# remote_v3.net
KiCad netlist of a schematic drawn in EAGLE
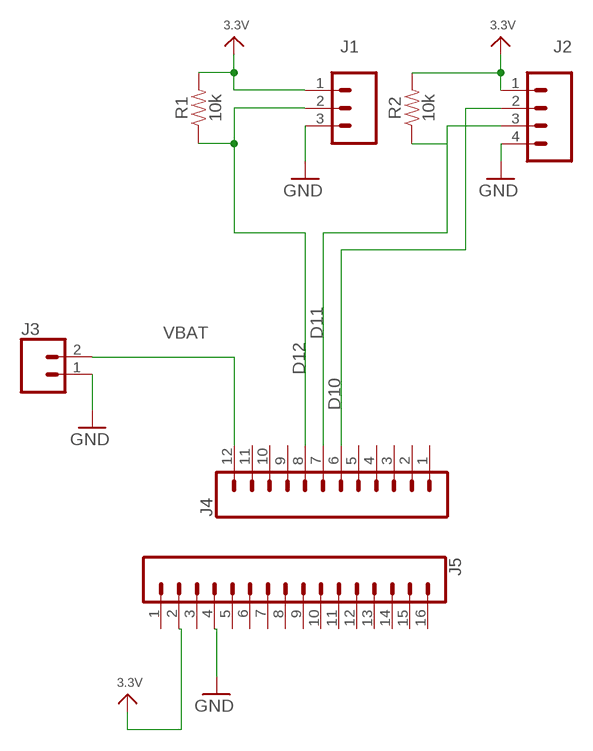
[diagram p0: schematic, sheet 1]

(export (version "E")
  (design (tool "Eeschema 10.0.6"))
  (components
    (comp (ref "J1")
      (value "CONN_03SCREW")
      (footprint "eagle-import:SCREWTERMINAL-3.5MM-3")
      (libsource (lib "eagle-import") (part "CONN_03SCREW"))
    )
    (comp (ref "J2")
      (value "CONN_04SCREW")
      (footprint "eagle-import:SCREWTERMINAL-3.5MM-4")
      (libsource (lib "eagle-import") (part "CONN_04SCREW"))
    )
    (comp (ref "J3")
      (value "CONN_023.5MM")
      (footprint "eagle-import:SCREWTERMINAL-3.5MM-2")
      (libsource (lib "eagle-import") (part "CONN_023.5MM"))
    )
    (comp (ref "J4")
      (value "CONN_12")
      (footprint "eagle-import:1X12")
      (libsource (lib "eagle-import") (part "CONN_12"))
    )
    (comp (ref "J5")
      (value "CONN_16")
      (footprint "eagle-import:1X16")
      (libsource (lib "eagle-import") (part "CONN_16"))
    )
    (comp (ref "R1")
      (value "10k")
      (footprint "eagle-import:AXIAL-0.3")
      (libsource (lib "eagle-import") (part "10KOHM-HORIZ-1/4W-1%"))
    )
    (comp (ref "R2")
      (value "10k")
      (footprint "eagle-import:AXIAL-0.3")
      (libsource (lib "eagle-import") (part "10KOHM-HORIZ-1/4W-1%"))
    )
  )
  (nets
    (net (code "1") (name "/D10") (class "Default")
      (node (ref "J2") (pin "2") (pinfunction "2_2") (pintype "passive"))
      (node (ref "J4") (pin "6") (pinfunction "6_6") (pintype "passive"))
    )
    (net (code "2") (name "/D11") (class "Default")
      (node (ref "J2") (pin "3") (pinfunction "3_3") (pintype "passive"))
      (node (ref "J4") (pin "7") (pinfunction "7_7") (pintype "passive"))
      (node (ref "R2") (pin "P$1") (pinfunction "1_P$1") (pintype "passive"))
    )
    (net (code "3") (name "/D12") (class "Default")
      (node (ref "J1") (pin "2") (pinfunction "2_2") (pintype "passive"))
      (node (ref "J4") (pin "8") (pinfunction "8_8") (pintype "passive"))
      (node (ref "R1") (pin "P$1") (pinfunction "1_P$1") (pintype "passive"))
    )
    (net (code "4") (name "/VBAT") (class "Default")
      (node (ref "J3") (pin "2") (pinfunction "2_2") (pintype "passive"))
      (node (ref "J4") (pin "12") (pinfunction "12_12") (pintype "passive"))
    )
    (net (code "5") (name "3.3V") (class "Default")
      (node (ref "J1") (pin "1") (pinfunction "1_1") (pintype "passive"))
      (node (ref "J2") (pin "1") (pinfunction "1_1") (pintype "passive"))
      (node (ref "J5") (pin "2") (pinfunction "2_2") (pintype "passive"))
      (node (ref "R1") (pin "P$2") (pinfunction "2_P$2") (pintype "passive"))
      (node (ref "R2") (pin "P$2") (pinfunction "2_P$2") (pintype "passive"))
    )
    (net (code "6") (name "GND") (class "Default")
      (node (ref "J1") (pin "3") (pinfunction "3_3") (pintype "passive"))
      (node (ref "J2") (pin "4") (pinfunction "4_4") (pintype "passive"))
      (node (ref "J3") (pin "1") (pinfunction "1_1") (pintype "passive"))
      (node (ref "J5") (pin "4") (pinfunction "4_4") (pintype "passive"))
    )
    (net (code "7") (name "unconnected-(J4-Pad1)") (class "Default")
      (node (ref "J4") (pin "1") (pinfunction "1_1") (pintype "passive"))
    )
    (net (code "8") (name "unconnected-(J4-Pad2)") (class "Default")
      (node (ref "J4") (pin "2") (pinfunction "2_2") (pintype "passive"))
    )
    (net (code "9") (name "unconnected-(J4-Pad3)") (class "Default")
      (node (ref "J4") (pin "3") (pinfunction "3_3") (pintype "passive"))
    )
    (net (code "10") (name "unconnected-(J4-Pad4)") (class "Default")
      (node (ref "J4") (pin "4") (pinfunction "4_4") (pintype "passive"))
    )
    (net (code "11") (name "unconnected-(J4-Pad5)") (class "Default")
      (node (ref "J4") (pin "5") (pinfunction "5_5") (pintype "passive"))
    )
    (net (code "12") (name "unconnected-(J4-Pad9)") (class "Default")
      (node (ref "J4") (pin "9") (pinfunction "9_9") (pintype "passive"))
    )
    (net (code "13") (name "unconnected-(J4-Pad10)") (class "Default")
      (node (ref "J4") (pin "10") (pinfunction "10_10") (pintype "passive"))
    )
    (net (code "14") (name "unconnected-(J4-Pad11)") (class "Default")
      (node (ref "J4") (pin "11") (pinfunction "11_11") (pintype "passive"))
    )
    (net (code "15") (name "unconnected-(J5-Pad1)") (class "Default")
      (node (ref "J5") (pin "1") (pinfunction "1_1") (pintype "passive"))
    )
    (net (code "16") (name "unconnected-(J5-Pad3)") (class "Default")
      (node (ref "J5") (pin "3") (pinfunction "3_3") (pintype "passive"))
    )
    (net (code "17") (name "unconnected-(J5-Pad5)") (class "Default")
      (node (ref "J5") (pin "5") (pinfunction "5_5") (pintype "passive"))
    )
    (net (code "18") (name "unconnected-(J5-Pad6)") (class "Default")
      (node (ref "J5") (pin "6") (pinfunction "6_6") (pintype "passive"))
    )
    (net (code "19") (name "unconnected-(J5-Pad7)") (class "Default")
      (node (ref "J5") (pin "7") (pinfunction "7_7") (pintype "passive"))
    )
    (net (code "20") (name "unconnected-(J5-Pad8)") (class "Default")
      (node (ref "J5") (pin "8") (pinfunction "8_8") (pintype "passive"))
    )
    (net (code "21") (name "unconnected-(J5-Pad9)") (class "Default")
      (node (ref "J5") (pin "9") (pinfunction "9_9") (pintype "passive"))
    )
    (net (code "22") (name "unconnected-(J5-Pad10)") (class "Default")
      (node (ref "J5") (pin "10") (pinfunction "10_10") (pintype "passive"))
    )
    (net (code "23") (name "unconnected-(J5-Pad11)") (class "Default")
      (node (ref "J5") (pin "11") (pinfunction "11_11") (pintype "passive"))
    )
    (net (code "24") (name "unconnected-(J5-Pad12)") (class "Default")
      (node (ref "J5") (pin "12") (pinfunction "12_12") (pintype "passive"))
    )
    (net (code "25") (name "unconnected-(J5-Pad13)") (class "Default")
      (node (ref "J5") (pin "13") (pinfunction "13_13") (pintype "passive"))
    )
    (net (code "26") (name "unconnected-(J5-Pad14)") (class "Default")
      (node (ref "J5") (pin "14") (pinfunction "14_14") (pintype "passive"))
    )
    (net (code "27") (name "unconnected-(J5-Pad15)") (class "Default")
      (node (ref "J5") (pin "15") (pinfunction "15_15") (pintype "passive"))
    )
    (net (code "28") (name "unconnected-(J5-Pad16)") (class "Default")
      (node (ref "J5") (pin "16") (pinfunction "16_16") (pintype "passive"))
    )
  )
)
